# DAC.net
KiCad netlist of a schematic drawn in EAGLE
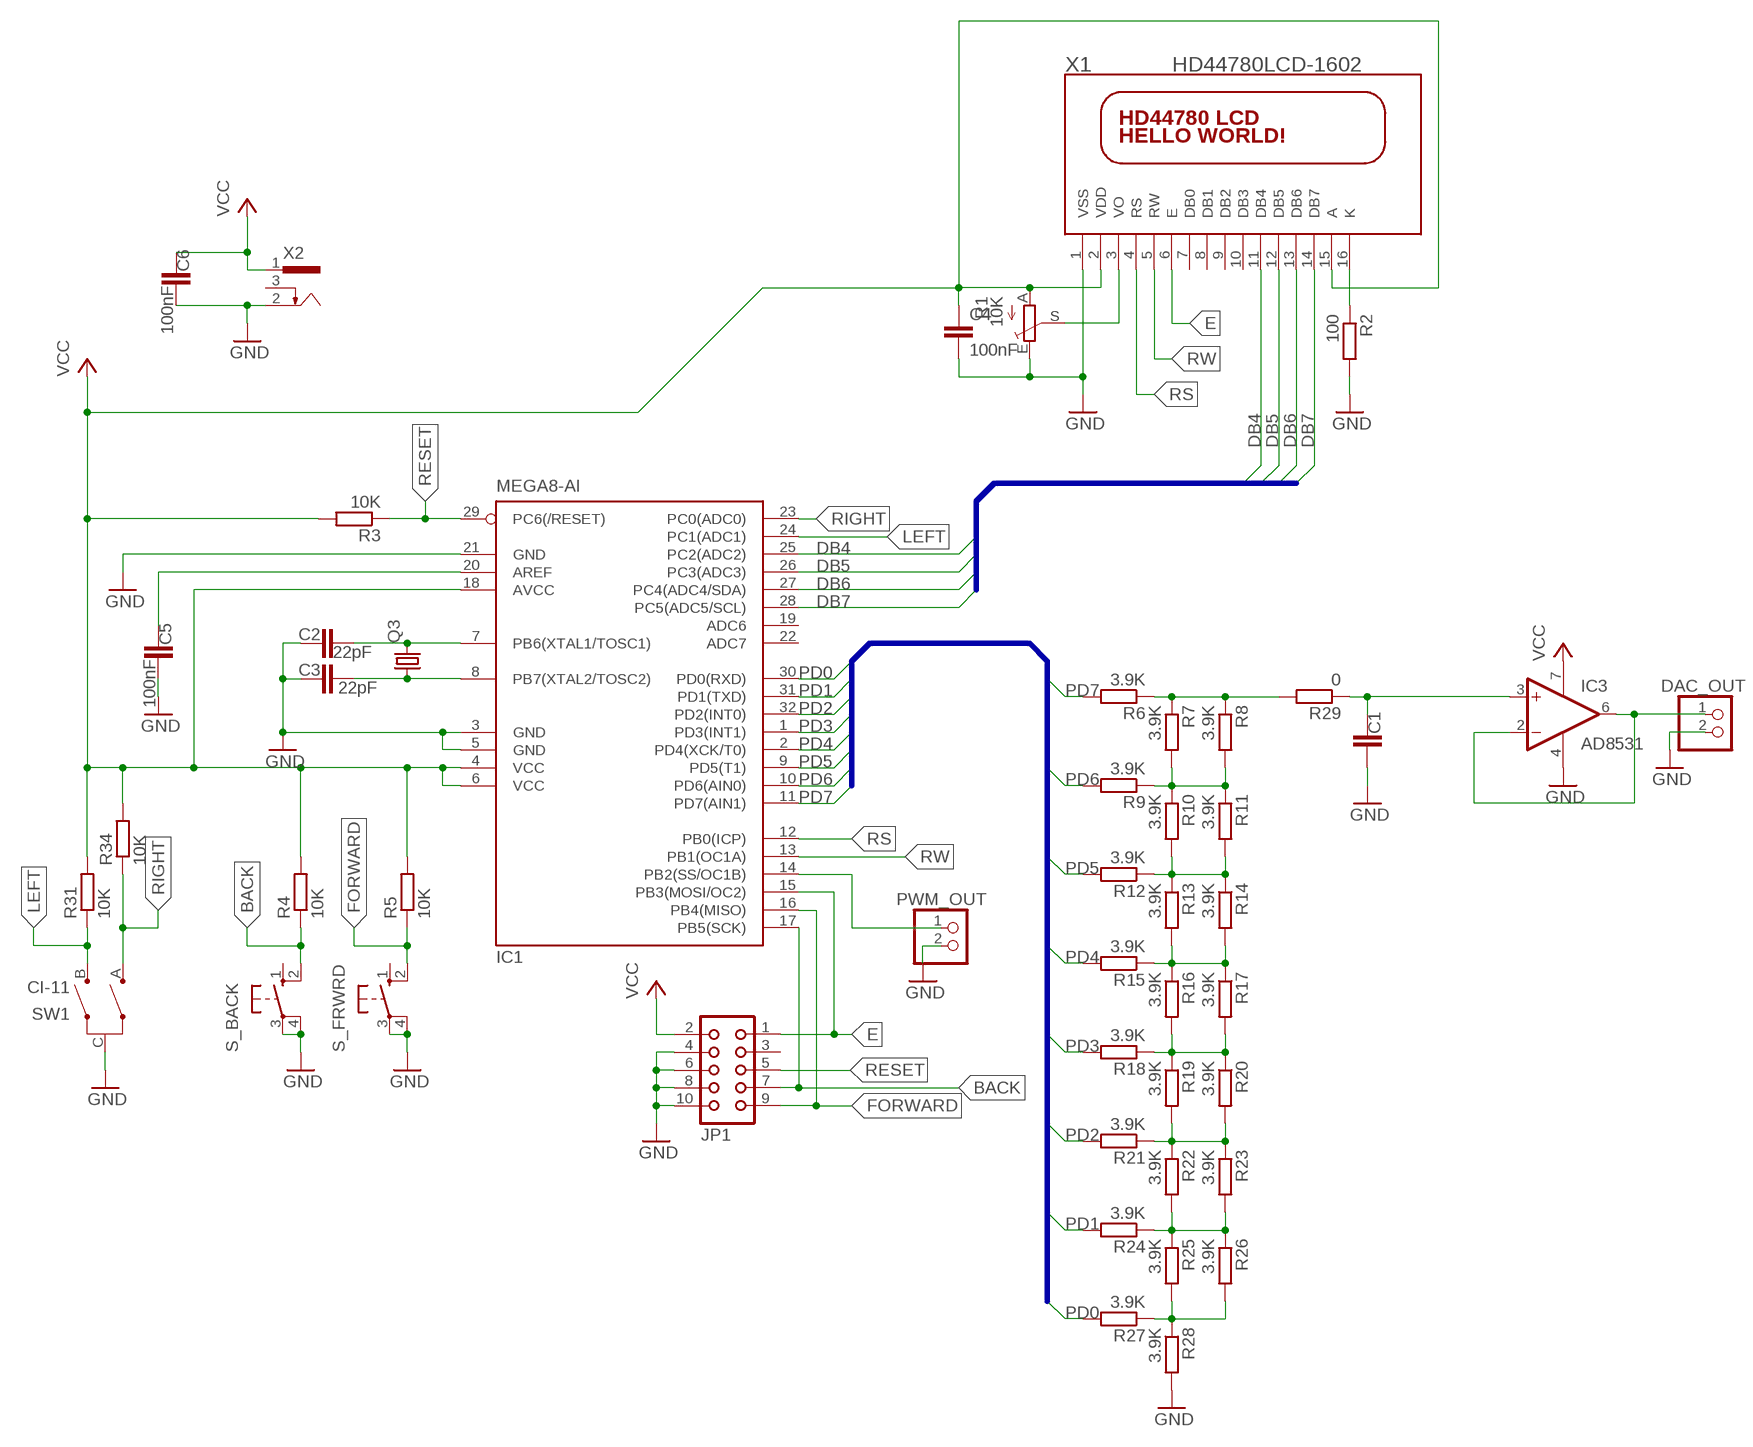
[diagram p0: schematic, sheet 1]

(export (version "E")
  (design (tool "Eeschema 10.0.6"))
  (components
    (comp (ref "C1")
      (value "C-EUC1206")
      (footprint "eagle-import:C1206")
      (libsource (lib "eagle-import") (part "C-EUC1206"))
    )
    (comp (ref "C2")
      (value "22pF")
      (footprint "eagle-import:C1206")
      (libsource (lib "eagle-import") (part "C-EUC1206"))
    )
    (comp (ref "C3")
      (value "22pF")
      (footprint "eagle-import:C1206")
      (libsource (lib "eagle-import") (part "C-EUC1206"))
    )
    (comp (ref "C4")
      (value "100nF")
      (footprint "eagle-import:C1206")
      (libsource (lib "eagle-import") (part "C-EUC1206"))
    )
    (comp (ref "C5")
      (value "100nF")
      (footprint "eagle-import:C1206")
      (libsource (lib "eagle-import") (part "C-EUC1206"))
    )
    (comp (ref "C6")
      (value "100nF")
      (footprint "eagle-import:C1206")
      (libsource (lib "eagle-import") (part "C-EUC1206"))
    )
    (comp (ref "DAC_OUT")
      (value "PINHD-1X2_2.54-90°")
      (footprint "eagle-import:1X02_90")
      (libsource (lib "eagle-import") (part "PINHD-1X2_2.54-90°"))
    )
    (comp (ref "IC1")
      (value "MEGA8-AI")
      (footprint "eagle-import:TQFP32-08")
      (fields (field (name "MPN") "ATMEGA8-16AU"))
      (libsource (lib "eagle-import") (part "MEGA8-AI"))
    )
    (comp (ref "IC3")
      (value "AD8531")
      (footprint "eagle-import:SO08")
      (libsource (lib "eagle-import") (part "MCP601SN"))
    )
    (comp (ref "JP1")
      (value "CON10L")
      (footprint "eagle-import:CON10L")
      (libsource (lib "eagle-import") (part "CON10L"))
    )
    (comp (ref "PWM_OUT")
      (value "PINHD-1X2_2.54-90°")
      (footprint "eagle-import:1X02_90")
      (libsource (lib "eagle-import") (part "PINHD-1X2_2.54-90°"))
    )
    (comp (ref "Q3")
      (value "CRYSTALHC49U-V")
      (footprint "eagle-import:HC49U-V")
      (libsource (lib "eagle-import") (part "CRYSTALHC49U-V"))
    )
    (comp (ref "R1")
      (value "10K")
      (footprint "eagle-import:CA6V")
      (libsource (lib "eagle-import") (part "TRIM_EU-CA6V"))
    )
    (comp (ref "R2")
      (value "100")
      (footprint "eagle-import:R1206")
      (libsource (lib "eagle-import") (part "R-EU_R1206"))
    )
    (comp (ref "R3")
      (value "10K")
      (footprint "eagle-import:R1206")
      (libsource (lib "eagle-import") (part "R-EU_R1206"))
    )
    (comp (ref "R4")
      (value "10K")
      (footprint "eagle-import:R1206")
      (libsource (lib "eagle-import") (part "R-EU_R1206"))
    )
    (comp (ref "R5")
      (value "10K")
      (footprint "eagle-import:R1206")
      (libsource (lib "eagle-import") (part "R-EU_R1206"))
    )
    (comp (ref "R6")
      (value "3.9K")
      (footprint "eagle-import:R1206")
      (libsource (lib "eagle-import") (part "R-EU_R1206"))
    )
    (comp (ref "R7")
      (value "3.9K")
      (footprint "eagle-import:R1206")
      (libsource (lib "eagle-import") (part "R-EU_R1206"))
    )
    (comp (ref "R8")
      (value "3.9K")
      (footprint "eagle-import:R1206")
      (libsource (lib "eagle-import") (part "R-EU_R1206"))
    )
    (comp (ref "R9")
      (value "3.9K")
      (footprint "eagle-import:R1206")
      (libsource (lib "eagle-import") (part "R-EU_R1206"))
    )
    (comp (ref "R10")
      (value "3.9K")
      (footprint "eagle-import:R1206")
      (libsource (lib "eagle-import") (part "R-EU_R1206"))
    )
    (comp (ref "R11")
      (value "3.9K")
      (footprint "eagle-import:R1206")
      (libsource (lib "eagle-import") (part "R-EU_R1206"))
    )
    (comp (ref "R12")
      (value "3.9K")
      (footprint "eagle-import:R1206")
      (libsource (lib "eagle-import") (part "R-EU_R1206"))
    )
    (comp (ref "R13")
      (value "3.9K")
      (footprint "eagle-import:R1206")
      (libsource (lib "eagle-import") (part "R-EU_R1206"))
    )
    (comp (ref "R14")
      (value "3.9K")
      (footprint "eagle-import:R1206")
      (libsource (lib "eagle-import") (part "R-EU_R1206"))
    )
    (comp (ref "R15")
      (value "3.9K")
      (footprint "eagle-import:R1206")
      (libsource (lib "eagle-import") (part "R-EU_R1206"))
    )
    (comp (ref "R16")
      (value "3.9K")
      (footprint "eagle-import:R1206")
      (libsource (lib "eagle-import") (part "R-EU_R1206"))
    )
    (comp (ref "R17")
      (value "3.9K")
      (footprint "eagle-import:R1206")
      (libsource (lib "eagle-import") (part "R-EU_R1206"))
    )
    (comp (ref "R18")
      (value "3.9K")
      (footprint "eagle-import:R1206")
      (libsource (lib "eagle-import") (part "R-EU_R1206"))
    )
    (comp (ref "R19")
      (value "3.9K")
      (footprint "eagle-import:R1206")
      (libsource (lib "eagle-import") (part "R-EU_R1206"))
    )
    (comp (ref "R20")
      (value "3.9K")
      (footprint "eagle-import:R1206")
      (libsource (lib "eagle-import") (part "R-EU_R1206"))
    )
    (comp (ref "R21")
      (value "3.9K")
      (footprint "eagle-import:R1206")
      (libsource (lib "eagle-import") (part "R-EU_R1206"))
    )
    (comp (ref "R22")
      (value "3.9K")
      (footprint "eagle-import:R1206")
      (libsource (lib "eagle-import") (part "R-EU_R1206"))
    )
    (comp (ref "R23")
      (value "3.9K")
      (footprint "eagle-import:R1206")
      (libsource (lib "eagle-import") (part "R-EU_R1206"))
    )
    (comp (ref "R24")
      (value "3.9K")
      (footprint "eagle-import:R1206")
      (libsource (lib "eagle-import") (part "R-EU_R1206"))
    )
    (comp (ref "R25")
      (value "3.9K")
      (footprint "eagle-import:R1206")
      (libsource (lib "eagle-import") (part "R-EU_R1206"))
    )
    (comp (ref "R26")
      (value "3.9K")
      (footprint "eagle-import:R1206")
      (libsource (lib "eagle-import") (part "R-EU_R1206"))
    )
    (comp (ref "R27")
      (value "3.9K")
      (footprint "eagle-import:R1206")
      (libsource (lib "eagle-import") (part "R-EU_R1206"))
    )
    (comp (ref "R28")
      (value "3.9K")
      (footprint "eagle-import:R1206")
      (libsource (lib "eagle-import") (part "R-EU_R1206"))
    )
    (comp (ref "R29")
      (value "0")
      (footprint "eagle-import:R1206")
      (libsource (lib "eagle-import") (part "R-EU_R1206"))
    )
    (comp (ref "R31")
      (value "10K")
      (footprint "eagle-import:R1206")
      (libsource (lib "eagle-import") (part "R-EU_R1206"))
    )
    (comp (ref "R34")
      (value "10K")
      (footprint "eagle-import:R1206")
      (libsource (lib "eagle-import") (part "R-EU_R1206"))
    )
    (comp (ref "SW1")
      (value "CI-11")
      (footprint "eagle-import:CI-11")
      (libsource (lib "eagle-import") (part "CI-11"))
    )
    (comp (ref "S_BACK")
      (value "10-XX")
      (footprint "eagle-import:B3F-10XX")
      (fields (field (name "MPN") "B3F-1000"))
      (libsource (lib "eagle-import") (part "10-XX"))
    )
    (comp (ref "S_FRWRD")
      (value "10-XX")
      (footprint "eagle-import:B3F-10XX")
      (fields (field (name "MPN") "B3F-1000"))
      (libsource (lib "eagle-import") (part "10-XX"))
    )
    (comp (ref "X1")
      (value "HD44780LCD-1602")
      (footprint "eagle-import:LCD1602")
      (libsource (lib "eagle-import") (part "HD44780LCD-1602"))
    )
    (comp (ref "X2")
      (value "733989-5")
      (footprint "eagle-import:733989-5")
      (libsource (lib "eagle-import") (part "73398?9-5"))
    )
  )
  (nets
    (net (code "1") (name "/DB4") (class "Default")
      (node (ref "IC1") (pin "25") (pinfunction "PC2(ADC2)_25") (pintype "bidirectional"))
      (node (ref "X1") (pin "11") (pinfunction "DB4_11") (pintype "bidirectional"))
    )
    (net (code "2") (name "/DB5") (class "Default")
      (node (ref "IC1") (pin "26") (pinfunction "PC3(ADC3)_26") (pintype "bidirectional"))
      (node (ref "X1") (pin "12") (pinfunction "DB5_12") (pintype "bidirectional"))
    )
    (net (code "3") (name "/DB6") (class "Default")
      (node (ref "IC1") (pin "27") (pinfunction "PC4(ADC4/SDA)_27") (pintype "bidirectional"))
      (node (ref "X1") (pin "13") (pinfunction "DB6_13") (pintype "bidirectional"))
    )
    (net (code "4") (name "/DB7") (class "Default")
      (node (ref "IC1") (pin "28") (pinfunction "PC5(ADC5/SCL)_28") (pintype "bidirectional"))
      (node (ref "X1") (pin "14") (pinfunction "DB7_14") (pintype "bidirectional"))
    )
    (net (code "5") (name "/PD0") (class "Default")
      (node (ref "IC1") (pin "30") (pinfunction "PD0(RXD)_30") (pintype "bidirectional"))
      (node (ref "R27") (pin "2") (pinfunction "2_2") (pintype "passive"))
    )
    (net (code "6") (name "/PD1") (class "Default")
      (node (ref "IC1") (pin "31") (pinfunction "PD1(TXD)_31") (pintype "bidirectional"))
      (node (ref "R24") (pin "2") (pinfunction "2_2") (pintype "passive"))
    )
    (net (code "7") (name "/PD2") (class "Default")
      (node (ref "IC1") (pin "32") (pinfunction "PD2(INT0)_32") (pintype "bidirectional"))
      (node (ref "R21") (pin "2") (pinfunction "2_2") (pintype "passive"))
    )
    (net (code "8") (name "/PD3") (class "Default")
      (node (ref "IC1") (pin "1") (pinfunction "PD3(INT1)_1") (pintype "bidirectional"))
      (node (ref "R18") (pin "2") (pinfunction "2_2") (pintype "passive"))
    )
    (net (code "9") (name "/PD4") (class "Default")
      (node (ref "IC1") (pin "2") (pinfunction "PD4(XCK/T0)_2") (pintype "bidirectional"))
      (node (ref "R15") (pin "2") (pinfunction "2_2") (pintype "passive"))
    )
    (net (code "10") (name "/PD5") (class "Default")
      (node (ref "IC1") (pin "9") (pinfunction "PD5(T1)_9") (pintype "bidirectional"))
      (node (ref "R12") (pin "2") (pinfunction "2_2") (pintype "passive"))
    )
    (net (code "11") (name "/PD6") (class "Default")
      (node (ref "IC1") (pin "10") (pinfunction "PD6(AIN0)_10") (pintype "bidirectional"))
      (node (ref "R9") (pin "2") (pinfunction "2_2") (pintype "passive"))
    )
    (net (code "12") (name "/PD7") (class "Default")
      (node (ref "IC1") (pin "11") (pinfunction "PD7(AIN1)_11") (pintype "bidirectional"))
      (node (ref "R6") (pin "2") (pinfunction "2_2") (pintype "passive"))
    )
    (net (code "13") (name "BACK") (class "Default")
      (node (ref "IC1") (pin "17") (pinfunction "PB5(SCK)_17") (pintype "bidirectional"))
      (node (ref "JP1") (pin "7") (pinfunction "7_7") (pintype "passive"))
      (node (ref "R4") (pin "1") (pinfunction "1_1") (pintype "passive"))
      (node (ref "S_BACK") (pin "2") (pinfunction "S1_2") (pintype "passive"))
    )
    (net (code "14") (name "E") (class "Default")
      (node (ref "IC1") (pin "15") (pinfunction "PB3(MOSI/OC2)_15") (pintype "bidirectional"))
      (node (ref "JP1") (pin "1") (pinfunction "1_1") (pintype "passive"))
      (node (ref "X1") (pin "6") (pinfunction "E_6") (pintype "input"))
    )
    (net (code "15") (name "FORWARD") (class "Default")
      (node (ref "IC1") (pin "16") (pinfunction "PB4(MISO)_16") (pintype "bidirectional"))
      (node (ref "JP1") (pin "9") (pinfunction "9_9") (pintype "passive"))
      (node (ref "R5") (pin "1") (pinfunction "1_1") (pintype "passive"))
      (node (ref "S_FRWRD") (pin "2") (pinfunction "S1_2") (pintype "passive"))
    )
    (net (code "16") (name "GND") (class "Default")
      (node (ref "C1") (pin "2") (pinfunction "2_2") (pintype "passive"))
      (node (ref "C2") (pin "1") (pinfunction "1_1") (pintype "passive"))
      (node (ref "C3") (pin "1") (pinfunction "1_1") (pintype "passive"))
      (node (ref "C4") (pin "2") (pinfunction "2_2") (pintype "passive"))
      (node (ref "C5") (pin "2") (pinfunction "2_2") (pintype "passive"))
      (node (ref "C6") (pin "2") (pinfunction "2_2") (pintype "passive"))
      (node (ref "DAC_OUT") (pin "2") (pinfunction "2_2") (pintype "passive"))
      (node (ref "IC1") (pin "21") (pinfunction "GND_21") (pintype "power_in"))
      (node (ref "IC1") (pin "3") (pinfunction "GND_3") (pintype "power_in"))
      (node (ref "IC1") (pin "5") (pinfunction "GND_5") (pintype "power_in"))
      (node (ref "IC3") (pin "4") (pinfunction "V-_4") (pintype "power_in"))
      (node (ref "JP1") (pin "10") (pinfunction "10_10") (pintype "passive"))
      (node (ref "JP1") (pin "4") (pinfunction "4_4") (pintype "passive"))
      (node (ref "JP1") (pin "6") (pinfunction "6_6") (pintype "passive"))
      (node (ref "JP1") (pin "8") (pinfunction "8_8") (pintype "passive"))
      (node (ref "PWM_OUT") (pin "2") (pinfunction "2_2") (pintype "passive"))
      (node (ref "R1") (pin "E") (pinfunction "E_E") (pintype "passive"))
      (node (ref "R2") (pin "2") (pinfunction "2_2") (pintype "passive"))
      (node (ref "R28") (pin "2") (pinfunction "2_2") (pintype "passive"))
      (node (ref "SW1") (pin "C") (pinfunction "C_C") (pintype "passive"))
      (node (ref "S_BACK") (pin "3") (pinfunction "P_3") (pintype "passive"))
      (node (ref "S_BACK") (pin "4") (pinfunction "P1_4") (pintype "passive"))
      (node (ref "S_FRWRD") (pin "3") (pinfunction "P_3") (pintype "passive"))
      (node (ref "S_FRWRD") (pin "4") (pinfunction "P1_4") (pintype "passive"))
      (node (ref "X1") (pin "1") (pinfunction "VSS_1") (pintype "power_in"))
      (node (ref "X2") (pin "2") (pinfunction "2_2") (pintype "passive"))
    )
    (net (code "17") (name "LEFT") (class "Default")
      (node (ref "IC1") (pin "24") (pinfunction "PC1(ADC1)_24") (pintype "bidirectional"))
      (node (ref "R31") (pin "1") (pinfunction "1_1") (pintype "passive"))
      (node (ref "SW1") (pin "B") (pinfunction "B_B") (pintype "passive"))
    )
    (net (code "18") (name "Net-(IC1-AREF)") (class "Default")
      (node (ref "C5") (pin "1") (pinfunction "1_1") (pintype "passive"))
      (node (ref "IC1") (pin "20") (pinfunction "AREF_20") (pintype "passive"))
    )
    (net (code "19") (name "Net-(IC1-PB2(SS{slash}OC1B))") (class "Default")
      (node (ref "IC1") (pin "14") (pinfunction "PB2(SS/OC1B)_14") (pintype "bidirectional"))
      (node (ref "PWM_OUT") (pin "1") (pinfunction "1_1") (pintype "passive"))
    )
    (net (code "20") (name "Net-(IC1-PB6(XTAL1{slash}TOSC1))") (class "Default")
      (node (ref "C2") (pin "2") (pinfunction "2_2") (pintype "passive"))
      (node (ref "IC1") (pin "7") (pinfunction "PB6(XTAL1/TOSC1)_7") (pintype "bidirectional"))
      (node (ref "Q3") (pin "2") (pinfunction "2_2") (pintype "passive"))
    )
    (net (code "21") (name "Net-(IC1-PB7(XTAL2{slash}TOSC2))") (class "Default")
      (node (ref "C3") (pin "2") (pinfunction "2_2") (pintype "passive"))
      (node (ref "IC1") (pin "8") (pinfunction "PB7(XTAL2/TOSC2)_8") (pintype "bidirectional"))
      (node (ref "Q3") (pin "1") (pinfunction "1_1") (pintype "passive"))
    )
    (net (code "22") (name "Net-(IC3-+IN)") (class "Default")
      (node (ref "C1") (pin "1") (pinfunction "1_1") (pintype "passive"))
      (node (ref "IC3") (pin "3") (pinfunction "+IN_3") (pintype "input"))
      (node (ref "R29") (pin "1") (pinfunction "1_1") (pintype "passive"))
    )
    (net (code "23") (name "Net-(IC3--IN)") (class "Default")
      (node (ref "DAC_OUT") (pin "1") (pinfunction "1_1") (pintype "passive"))
      (node (ref "IC3") (pin "2") (pinfunction "-IN_2") (pintype "input"))
      (node (ref "IC3") (pin "6") (pinfunction "OUT_6") (pintype "output"))
    )
    (net (code "24") (name "Net-(R10-Pad1)") (class "Default")
      (node (ref "R10") (pin "1") (pinfunction "1_1") (pintype "passive"))
      (node (ref "R11") (pin "1") (pinfunction "1_1") (pintype "passive"))
      (node (ref "R7") (pin "2") (pinfunction "2_2") (pintype "passive"))
      (node (ref "R8") (pin "2") (pinfunction "2_2") (pintype "passive"))
      (node (ref "R9") (pin "1") (pinfunction "1_1") (pintype "passive"))
    )
    (net (code "25") (name "Net-(R10-Pad2)") (class "Default")
      (node (ref "R10") (pin "2") (pinfunction "2_2") (pintype "passive"))
      (node (ref "R11") (pin "2") (pinfunction "2_2") (pintype "passive"))
      (node (ref "R12") (pin "1") (pinfunction "1_1") (pintype "passive"))
      (node (ref "R13") (pin "1") (pinfunction "1_1") (pintype "passive"))
      (node (ref "R14") (pin "1") (pinfunction "1_1") (pintype "passive"))
    )
    (net (code "26") (name "Net-(R13-Pad2)") (class "Default")
      (node (ref "R13") (pin "2") (pinfunction "2_2") (pintype "passive"))
      (node (ref "R14") (pin "2") (pinfunction "2_2") (pintype "passive"))
      (node (ref "R15") (pin "1") (pinfunction "1_1") (pintype "passive"))
      (node (ref "R16") (pin "1") (pinfunction "1_1") (pintype "passive"))
      (node (ref "R17") (pin "1") (pinfunction "1_1") (pintype "passive"))
    )
    (net (code "27") (name "Net-(R16-Pad2)") (class "Default")
      (node (ref "R16") (pin "2") (pinfunction "2_2") (pintype "passive"))
      (node (ref "R17") (pin "2") (pinfunction "2_2") (pintype "passive"))
      (node (ref "R18") (pin "1") (pinfunction "1_1") (pintype "passive"))
      (node (ref "R19") (pin "1") (pinfunction "1_1") (pintype "passive"))
      (node (ref "R20") (pin "1") (pinfunction "1_1") (pintype "passive"))
    )
    (net (code "28") (name "Net-(R19-Pad2)") (class "Default")
      (node (ref "R19") (pin "2") (pinfunction "2_2") (pintype "passive"))
      (node (ref "R20") (pin "2") (pinfunction "2_2") (pintype "passive"))
      (node (ref "R21") (pin "1") (pinfunction "1_1") (pintype "passive"))
      (node (ref "R22") (pin "1") (pinfunction "1_1") (pintype "passive"))
      (node (ref "R23") (pin "1") (pinfunction "1_1") (pintype "passive"))
    )
    (net (code "29") (name "Net-(R22-Pad2)") (class "Default")
      (node (ref "R22") (pin "2") (pinfunction "2_2") (pintype "passive"))
      (node (ref "R23") (pin "2") (pinfunction "2_2") (pintype "passive"))
      (node (ref "R24") (pin "1") (pinfunction "1_1") (pintype "passive"))
      (node (ref "R25") (pin "1") (pinfunction "1_1") (pintype "passive"))
      (node (ref "R26") (pin "1") (pinfunction "1_1") (pintype "passive"))
    )
    (net (code "30") (name "Net-(R25-Pad2)") (class "Default")
      (node (ref "R25") (pin "2") (pinfunction "2_2") (pintype "passive"))
      (node (ref "R26") (pin "2") (pinfunction "2_2") (pintype "passive"))
      (node (ref "R27") (pin "1") (pinfunction "1_1") (pintype "passive"))
      (node (ref "R28") (pin "1") (pinfunction "1_1") (pintype "passive"))
    )
    (net (code "31") (name "Net-(R29-Pad2)") (class "Default")
      (node (ref "R29") (pin "2") (pinfunction "2_2") (pintype "passive"))
      (node (ref "R6") (pin "1") (pinfunction "1_1") (pintype "passive"))
      (node (ref "R7") (pin "1") (pinfunction "1_1") (pintype "passive"))
      (node (ref "R8") (pin "1") (pinfunction "1_1") (pintype "passive"))
    )
    (net (code "32") (name "Net-(X1-K)") (class "Default")
      (node (ref "R2") (pin "1") (pinfunction "1_1") (pintype "passive"))
      (node (ref "X1") (pin "16") (pinfunction "K_16") (pintype "input"))
    )
    (net (code "33") (name "Net-(X1-VO)") (class "Default")
      (node (ref "R1") (pin "S") (pinfunction "S_S") (pintype "passive"))
      (node (ref "X1") (pin "3") (pinfunction "VO_3") (pintype "input"))
    )
    (net (code "34") (name "RESET") (class "Default")
      (node (ref "IC1") (pin "29") (pinfunction "PC6(/RESET)_29") (pintype "bidirectional"))
      (node (ref "JP1") (pin "5") (pinfunction "5_5") (pintype "passive"))
      (node (ref "R3") (pin "1") (pinfunction "1_1") (pintype "passive"))
    )
    (net (code "35") (name "RIGHT") (class "Default")
      (node (ref "IC1") (pin "23") (pinfunction "PC0(ADC0)_23") (pintype "bidirectional"))
      (node (ref "R34") (pin "1") (pinfunction "1_1") (pintype "passive"))
      (node (ref "SW1") (pin "A") (pinfunction "A_A") (pintype "passive"))
    )
    (net (code "36") (name "RS") (class "Default")
      (node (ref "IC1") (pin "12") (pinfunction "PB0(ICP)_12") (pintype "bidirectional"))
      (node (ref "X1") (pin "4") (pinfunction "RS_4") (pintype "input"))
    )
    (net (code "37") (name "RW") (class "Default")
      (node (ref "IC1") (pin "13") (pinfunction "PB1(OC1A)_13") (pintype "bidirectional"))
      (node (ref "X1") (pin "5") (pinfunction "RW_5") (pintype "input"))
    )
    (net (code "38") (name "VCC") (class "Default")
      (node (ref "C4") (pin "1") (pinfunction "1_1") (pintype "passive"))
      (node (ref "C6") (pin "1") (pinfunction "1_1") (pintype "passive"))
      (node (ref "IC1") (pin "18") (pinfunction "AVCC_18") (pintype "power_in"))
      (node (ref "IC1") (pin "4") (pinfunction "VCC_4") (pintype "power_in"))
      (node (ref "IC1") (pin "6") (pinfunction "VCC_6") (pintype "power_in"))
      (node (ref "IC3") (pin "7") (pinfunction "V+_7") (pintype "power_in"))
      (node (ref "JP1") (pin "2") (pinfunction "2_2") (pintype "passive"))
      (node (ref "R1") (pin "A") (pinfunction "A_A") (pintype "passive"))
      (node (ref "R3") (pin "2") (pinfunction "2_2") (pintype "passive"))
      (node (ref "R31") (pin "2") (pinfunction "2_2") (pintype "passive"))
      (node (ref "R34") (pin "2") (pinfunction "2_2") (pintype "passive"))
      (node (ref "R4") (pin "2") (pinfunction "2_2") (pintype "passive"))
      (node (ref "R5") (pin "2") (pinfunction "2_2") (pintype "passive"))
      (node (ref "X1") (pin "15") (pinfunction "A_15") (pintype "input"))
      (node (ref "X1") (pin "2") (pinfunction "VDD_2") (pintype "power_in"))
      (node (ref "X2") (pin "1") (pinfunction "1_1") (pintype "passive"))
    )
    (net (code "39") (name "unconnected-(IC1-ADC6-Pad19)") (class "Default")
      (node (ref "IC1") (pin "19") (pinfunction "ADC6_19") (pintype "bidirectional"))
    )
    (net (code "40") (name "unconnected-(IC1-ADC7-Pad22)") (class "Default")
      (node (ref "IC1") (pin "22") (pinfunction "ADC7_22") (pintype "bidirectional"))
    )
    (net (code "41") (name "unconnected-(JP1-Pad3)") (class "Default")
      (node (ref "JP1") (pin "3") (pinfunction "3_3") (pintype "passive"))
    )
    (net (code "42") (name "unconnected-(S_BACK-S-Pad1)") (class "Default")
      (node (ref "S_BACK") (pin "1") (pinfunction "S_1") (pintype "passive"))
    )
    (net (code "43") (name "unconnected-(S_FRWRD-S-Pad1)") (class "Default")
      (node (ref "S_FRWRD") (pin "1") (pinfunction "S_1") (pintype "passive"))
    )
    (net (code "44") (name "unconnected-(X1-DB0-Pad7)") (class "Default")
      (node (ref "X1") (pin "7") (pinfunction "DB0_7") (pintype "bidirectional"))
    )
    (net (code "45") (name "unconnected-(X1-DB1-Pad8)") (class "Default")
      (node (ref "X1") (pin "8") (pinfunction "DB1_8") (pintype "bidirectional"))
    )
    (net (code "46") (name "unconnected-(X1-DB2-Pad9)") (class "Default")
      (node (ref "X1") (pin "9") (pinfunction "DB2_9") (pintype "bidirectional"))
    )
    (net (code "47") (name "unconnected-(X1-DB3-Pad10)") (class "Default")
      (node (ref "X1") (pin "10") (pinfunction "DB3_10") (pintype "bidirectional"))
    )
    (net (code "48") (name "unconnected-(X2-Pad3)") (class "Default")
      (node (ref "X2") (pin "3") (pinfunction "3_3") (pintype "passive"))
    )
  )
)
